# design.net
KiCad netlist of a schematic drawn in Altium Designer
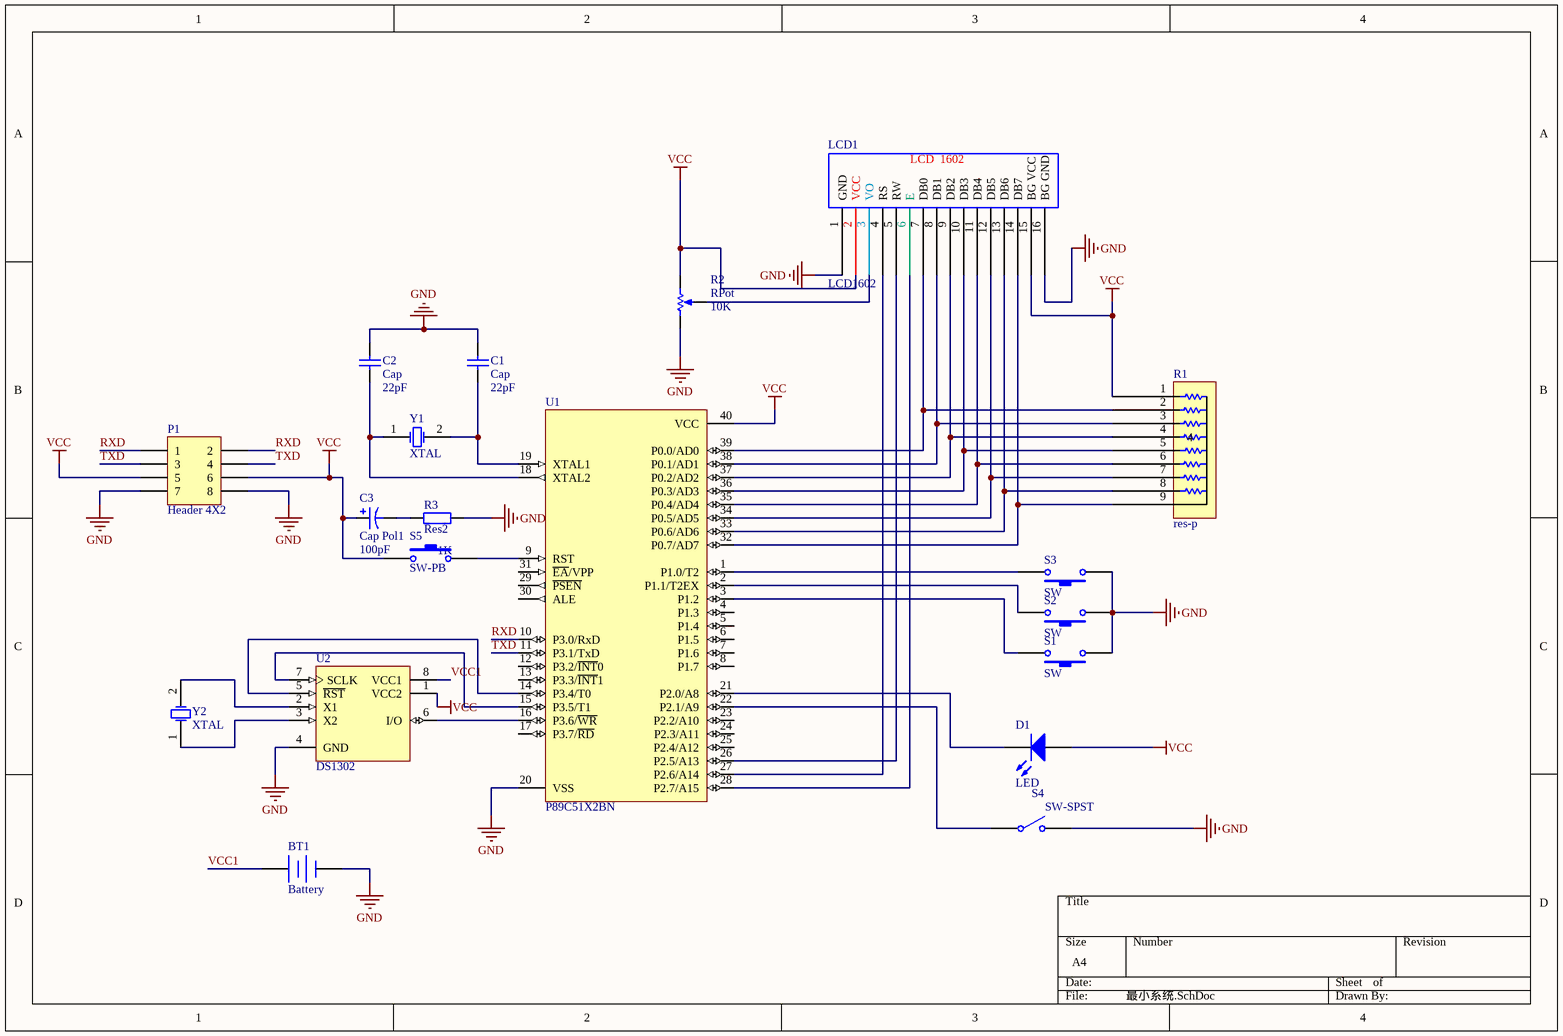
[diagram p0: 最小系统.SchDoc]

(export (version "E")
  (design (tool "Eeschema 10.0.6"))
  (components
    (comp (ref "BT1")
      (value "Battery")
      (footprint "BAT-2")
      (description "Multicell Battery")
      (fields (field (name "PUBLISHER") "Altium Limited"))
      (libsource (lib "Miscellaneous Devices") (part "Battery"))
    )
    (comp (ref "C1")
      (value "Cap")
      (footprint "CAPR2.54-5.1x3.2")
      (description "Capacitor")
      (fields (field (name "ALTIUM_VALUE") "22pF") (field (name "PUBLISHER") "Altium Limited"))
      (libsource (lib "Miscellaneous Devices") (part "Cap"))
    )
    (comp (ref "C2")
      (value "Cap")
      (footprint "CAPR2.54-5.1x3.2")
      (description "Capacitor")
      (fields (field (name "ALTIUM_VALUE") "22pF") (field (name "PUBLISHER") "Altium Limited"))
      (libsource (lib "Miscellaneous Devices") (part "Cap"))
    )
    (comp (ref "C3")
      (value "Cap Pol1")
      (footprint "RB7.6-15")
      (description "Polarized Capacitor (Radial)")
      (fields (field (name "ALTIUM_VALUE") "100pF") (field (name "PUBLISHER") "Altium Limited"))
      (libsource (lib "Miscellaneous Devices") (part "Cap Pol1"))
    )
    (comp (ref "D1") (value "LED") (footprint "LED-1") (libsource (lib "我的集成库库") (part "LED")))
    (comp (ref "LCD1") (value "LCD1602") (footprint "1602LCD") (libsource (lib "MyInt_Lib") (part "LCD1602")))
    (comp (ref "P1")
      (value "Header 4X2")
      (footprint "HDR2X4")
      (description "Header, 4-Pin, Dual row")
      (fields (field (name "PUBLISHER") "Altium Limited"))
      (libsource (lib "Miscellaneous Connectors") (part "Header 4X2"))
    )
    (comp (ref "R1") (value "res-p") (footprint "HDR1X9") (libsource (lib "我的集成库库") (part "res-p")))
    (comp (ref "R2")
      (value "RPot")
      (footprint "VR5")
      (description "Potentiometer")
      (fields (field (name "ALTIUM_VALUE") "10K") (field (name "PUBLISHER") "Altium Limited"))
      (libsource (lib "Miscellaneous Devices") (part "RPot"))
    )
    (comp (ref "R3")
      (value "Res2")
      (footprint "AXIAL-0.4")
      (description "Resistor")
      (fields (field (name "ALTIUM_VALUE") "1K") (field (name "PUBLISHER") "Altium Limited"))
      (libsource (lib "Miscellaneous Devices") (part "Res2"))
    )
    (comp (ref "S1") (value "SW") (footprint "SW/PB-V4/H7.1") (libsource (lib "我的集成库库") (part "SWITCH")))
    (comp (ref "S2") (value "SW") (footprint "SW/PB-V4/H7.1") (libsource (lib "我的集成库库") (part "SWITCH")))
    (comp (ref "S3") (value "SW") (footprint "SW/PB-V4/H7.1") (libsource (lib "我的集成库库") (part "SWITCH")))
    (comp (ref "S4")
      (value "SW-SPST")
      (footprint "SPST-2")
      (description "Single-Pole, Single-Throw Switch")
      (fields (field (name "PUBLISHER") "Altium Limited"))
      (libsource (lib "Miscellaneous Devices") (part "SW-SPST"))
    )
    (comp (ref "S5")
      (value "SW-PB")
      (footprint "SW/PB-V4/H7.1")
      (description "Switch")
      (fields (field (name "PUBLISHER") "Altium Limited"))
      (libsource (lib "Miscellaneous Devices") (part "SW-PB"))
    )
    (comp (ref "U1")
      (value "P89C51X2BN")
      (footprint "SOT129-1")
      (description "80C51 8-Bit Flash Microcontroller Family, 4 kB Flash")
      (fields (field (name "PUBLISHER") "Altium Limited"))
      (libsource (lib "Philips Microcontroller 8-Bit") (part "P89C51X2BN"))
    )
    (comp (ref "U2")
      (value "DS1302")
      (footprint "DIP8")
      (description "Trickle Charge Timekeeping Chip")
      (fields (field (name "PUBLISHER") "Altium Limited"))
      (libsource (lib "Dallas Peripheral Real Time Clock") (part "DS1302"))
    )
    (comp (ref "Y1")
      (value "XTAL")
      (footprint "BCY-W2/D3.1")
      (description "Crystal Oscillator")
      (fields (field (name "PUBLISHER") "Altium Limited"))
      (libsource (lib "Miscellaneous Devices") (part "XTAL"))
    )
    (comp (ref "Y2")
      (value "XTAL")
      (footprint "BCY-W2/D3.1")
      (description "Crystal Oscillator")
      (fields (field (name "PUBLISHER") "Altium Limited"))
      (libsource (lib "Miscellaneous Devices") (part "XTAL"))
    )
  )
  (nets
    (net (code "1") (name "/RXD") (class "Default")
      (node (ref "P1") (pin "1") (pinfunction "1_1") (pintype "passive"))
      (node (ref "P1") (pin "2") (pinfunction "2_2") (pintype "passive"))
      (node (ref "U1") (pin "10") (pinfunction "P3.0/RxD_10") (pintype "bidirectional"))
    )
    (net (code "2") (name "/TXD") (class "Default")
      (node (ref "P1") (pin "3") (pinfunction "3_3") (pintype "passive"))
      (node (ref "P1") (pin "4") (pinfunction "4_4") (pintype "passive"))
      (node (ref "U1") (pin "11") (pinfunction "P3.1/TxD_11") (pintype "bidirectional"))
    )
    (net (code "3") (name "/VCC1") (class "Default")
      (node (ref "BT1") (pin "1") (pinfunction "+_1") (pintype "passive"))
      (node (ref "U2") (pin "8") (pinfunction "VCC1_8") (pintype "power_in"))
    )
    (net (code "4") (name "GND") (class "Default")
      (node (ref "BT1") (pin "2") (pinfunction "-_2") (pintype "passive"))
      (node (ref "C1") (pin "2") (pinfunction "2_2") (pintype "passive"))
      (node (ref "C2") (pin "2") (pinfunction "2_2") (pintype "passive"))
      (node (ref "LCD1") (pin "1") (pinfunction "GND_1") (pintype "passive"))
      (node (ref "LCD1") (pin "16") (pinfunction "BG_GND_16") (pintype "passive"))
      (node (ref "P1") (pin "7") (pinfunction "7_7") (pintype "passive"))
      (node (ref "P1") (pin "8") (pinfunction "8_8") (pintype "passive"))
      (node (ref "R2") (pin "1") (pinfunction "TOP_1") (pintype "passive"))
      (node (ref "R3") (pin "2") (pinfunction "2_2") (pintype "passive"))
      (node (ref "S1") (pin "1") (pinfunction "1_1") (pintype "passive"))
      (node (ref "S2") (pin "1") (pinfunction "1_1") (pintype "passive"))
      (node (ref "S3") (pin "1") (pinfunction "1_1") (pintype "passive"))
      (node (ref "S4") (pin "2") (pinfunction "NO_2") (pintype "passive"))
      (node (ref "U1") (pin "20") (pinfunction "VSS_20") (pintype "power_in"))
      (node (ref "U2") (pin "4") (pinfunction "GND_4") (pintype "power_in"))
    )
    (net (code "5") (name "Net-(C3-Pad2)") (class "Default")
      (node (ref "C3") (pin "2") (pinfunction "2_2") (pintype "passive"))
      (node (ref "R3") (pin "1") (pinfunction "1_1") (pintype "passive"))
    )
    (net (code "6") (name "Net-(D1-K)") (class "Default")
      (node (ref "D1") (pin "2") (pinfunction "K_2") (pintype "passive"))
      (node (ref "U1") (pin "21") (pinfunction "P2.0/A8_21") (pintype "bidirectional"))
    )
    (net (code "7") (name "Net-(LCD1-DB0)") (class "Default")
      (node (ref "LCD1") (pin "7") (pinfunction "DB0_7") (pintype "passive"))
      (node (ref "R1") (pin "2") (pinfunction "2_2") (pintype "passive"))
      (node (ref "U1") (pin "39") (pinfunction "P0.0/AD0_39") (pintype "bidirectional"))
    )
    (net (code "8") (name "Net-(LCD1-DB1)") (class "Default")
      (node (ref "LCD1") (pin "8") (pinfunction "DB1_8") (pintype "passive"))
      (node (ref "R1") (pin "3") (pinfunction "3_3") (pintype "passive"))
      (node (ref "U1") (pin "38") (pinfunction "P0.1/AD1_38") (pintype "bidirectional"))
    )
    (net (code "9") (name "Net-(LCD1-DB2)") (class "Default")
      (node (ref "LCD1") (pin "9") (pinfunction "DB2_9") (pintype "passive"))
      (node (ref "R1") (pin "4") (pinfunction "4_4") (pintype "passive"))
      (node (ref "U1") (pin "37") (pinfunction "P0.2/AD2_37") (pintype "bidirectional"))
    )
    (net (code "10") (name "Net-(LCD1-DB3)") (class "Default")
      (node (ref "LCD1") (pin "10") (pinfunction "DB3_10") (pintype "passive"))
      (node (ref "R1") (pin "5") (pinfunction "5_5") (pintype "passive"))
      (node (ref "U1") (pin "36") (pinfunction "P0.3/AD3_36") (pintype "bidirectional"))
    )
    (net (code "11") (name "Net-(LCD1-DB4)") (class "Default")
      (node (ref "LCD1") (pin "11") (pinfunction "DB4_11") (pintype "passive"))
      (node (ref "R1") (pin "6") (pinfunction "6_6") (pintype "passive"))
      (node (ref "U1") (pin "35") (pinfunction "P0.4/AD4_35") (pintype "bidirectional"))
    )
    (net (code "12") (name "Net-(LCD1-DB5)") (class "Default")
      (node (ref "LCD1") (pin "12") (pinfunction "DB5_12") (pintype "passive"))
      (node (ref "R1") (pin "7") (pinfunction "7_7") (pintype "passive"))
      (node (ref "U1") (pin "34") (pinfunction "P0.5/AD5_34") (pintype "bidirectional"))
    )
    (net (code "13") (name "Net-(LCD1-DB6)") (class "Default")
      (node (ref "LCD1") (pin "13") (pinfunction "DB6_13") (pintype "passive"))
      (node (ref "R1") (pin "8") (pinfunction "8_8") (pintype "passive"))
      (node (ref "U1") (pin "33") (pinfunction "P0.6/AD6_33") (pintype "bidirectional"))
    )
    (net (code "14") (name "Net-(LCD1-DB7)") (class "Default")
      (node (ref "LCD1") (pin "14") (pinfunction "DB7_14") (pintype "passive"))
      (node (ref "R1") (pin "9") (pinfunction "9_9") (pintype "passive"))
      (node (ref "U1") (pin "32") (pinfunction "P0.7/AD7_32") (pintype "bidirectional"))
    )
    (net (code "15") (name "Net-(LCD1-E)") (class "Default")
      (node (ref "LCD1") (pin "6") (pinfunction "E_6") (pintype "passive"))
      (node (ref "U1") (pin "28") (pinfunction "P2.7/A15_28") (pintype "bidirectional"))
    )
    (net (code "16") (name "Net-(LCD1-RS)") (class "Default")
      (node (ref "LCD1") (pin "4") (pinfunction "RS_4") (pintype "passive"))
      (node (ref "U1") (pin "27") (pinfunction "P2.6/A14_27") (pintype "bidirectional"))
    )
    (net (code "17") (name "Net-(LCD1-RW)") (class "Default")
      (node (ref "LCD1") (pin "5") (pinfunction "RW_5") (pintype "passive"))
      (node (ref "U1") (pin "26") (pinfunction "P2.5/A13_26") (pintype "bidirectional"))
    )
    (net (code "18") (name "Net-(LCD1-VO)") (class "Default")
      (node (ref "LCD1") (pin "3") (pinfunction "VO_3") (pintype "passive"))
      (node (ref "R2") (pin "3") (pinfunction "TAP_3") (pintype "passive"))
    )
    (net (code "19") (name "Net-(S4-COMMON)") (class "Default")
      (node (ref "S4") (pin "1") (pinfunction "COMMON_1") (pintype "passive"))
      (node (ref "U1") (pin "22") (pinfunction "P2.1/A9_22") (pintype "bidirectional"))
    )
    (net (code "20") (name "Net-(U1-P1.0{slash}T2)") (class "Default")
      (node (ref "S3") (pin "2") (pinfunction "2_2") (pintype "passive"))
      (node (ref "U1") (pin "1") (pinfunction "P1.0/T2_1") (pintype "bidirectional"))
    )
    (net (code "21") (name "Net-(U1-P1.1{slash}T2EX)") (class "Default")
      (node (ref "S2") (pin "2") (pinfunction "2_2") (pintype "passive"))
      (node (ref "U1") (pin "2") (pinfunction "P1.1/T2EX_2") (pintype "bidirectional"))
    )
    (net (code "22") (name "Net-(U1-P1.2)") (class "Default")
      (node (ref "S1") (pin "2") (pinfunction "2_2") (pintype "passive"))
      (node (ref "U1") (pin "3") (pinfunction "P1.2_3") (pintype "bidirectional"))
    )
    (net (code "23") (name "Net-(U1-P3.4{slash}T0)") (class "Default")
      (node (ref "U1") (pin "14") (pinfunction "P3.4/T0_14") (pintype "bidirectional"))
      (node (ref "U2") (pin "5") (pinfunction "~{RST}_5") (pintype "input"))
    )
    (net (code "24") (name "Net-(U1-P3.5{slash}T1)") (class "Default")
      (node (ref "U1") (pin "15") (pinfunction "P3.5/T1_15") (pintype "bidirectional"))
      (node (ref "U2") (pin "7") (pinfunction "SCLK_7") (pintype "input"))
    )
    (net (code "25") (name "Net-(U1-P3.6{slash}~{WR})") (class "Default")
      (node (ref "U1") (pin "16") (pinfunction "P3.6/~{WR}_16") (pintype "bidirectional"))
      (node (ref "U2") (pin "6") (pinfunction "I/O_6") (pintype "bidirectional"))
    )
    (net (code "26") (name "Net-(U1-RST)") (class "Default")
      (node (ref "S5") (pin "2") (pinfunction "2_2") (pintype "passive"))
      (node (ref "U1") (pin "9") (pinfunction "RST_9") (pintype "input"))
    )
    (net (code "27") (name "Net-(U1-XTAL1)") (class "Default")
      (node (ref "C1") (pin "1") (pinfunction "1_1") (pintype "passive"))
      (node (ref "U1") (pin "19") (pinfunction "XTAL1_19") (pintype "input"))
      (node (ref "Y1") (pin "2") (pinfunction "OSC2_2") (pintype "passive"))
    )
    (net (code "28") (name "Net-(U1-XTAL2)") (class "Default")
      (node (ref "C2") (pin "1") (pinfunction "1_1") (pintype "passive"))
      (node (ref "U1") (pin "18") (pinfunction "XTAL2_18") (pintype "output"))
      (node (ref "Y1") (pin "1") (pinfunction "OSC1_1") (pintype "passive"))
    )
    (net (code "29") (name "Net-(U2-X1)") (class "Default")
      (node (ref "U2") (pin "2") (pinfunction "X1_2") (pintype "input"))
      (node (ref "Y2") (pin "2") (pinfunction "OSC2_2") (pintype "passive"))
    )
    (net (code "30") (name "Net-(U2-X2)") (class "Default")
      (node (ref "U2") (pin "3") (pinfunction "X2_3") (pintype "input"))
      (node (ref "Y2") (pin "1") (pinfunction "OSC1_1") (pintype "passive"))
    )
    (net (code "31") (name "VCC") (class "Default")
      (node (ref "C3") (pin "1") (pinfunction "1_1") (pintype "passive"))
      (node (ref "D1") (pin "1") (pinfunction "A_1") (pintype "passive"))
      (node (ref "LCD1") (pin "15") (pinfunction "BG_VCC_15") (pintype "passive"))
      (node (ref "LCD1") (pin "2") (pinfunction "VCC_2") (pintype "passive"))
      (node (ref "P1") (pin "5") (pinfunction "5_5") (pintype "passive"))
      (node (ref "P1") (pin "6") (pinfunction "6_6") (pintype "passive"))
      (node (ref "R1") (pin "1") (pinfunction "1_1") (pintype "passive"))
      (node (ref "R2") (pin "2") (pinfunction "BOT_2") (pintype "passive"))
      (node (ref "S5") (pin "1") (pinfunction "1_1") (pintype "passive"))
      (node (ref "U1") (pin "40") (pinfunction "VCC_40") (pintype "power_in"))
      (node (ref "U2") (pin "1") (pinfunction "VCC2_1") (pintype "power_in"))
    )
    (net (code "32") (name "unconnected-(U1-ALE-Pad30)") (class "Default")
      (node (ref "U1") (pin "30") (pinfunction "ALE_30") (pintype "output"))
    )
    (net (code "33") (name "unconnected-(U1-P1.3-Pad4)") (class "Default")
      (node (ref "U1") (pin "4") (pinfunction "P1.3_4") (pintype "bidirectional"))
    )
    (net (code "34") (name "unconnected-(U1-P1.4-Pad5)") (class "Default")
      (node (ref "U1") (pin "5") (pinfunction "P1.4_5") (pintype "bidirectional"))
    )
    (net (code "35") (name "unconnected-(U1-P1.5-Pad6)") (class "Default")
      (node (ref "U1") (pin "6") (pinfunction "P1.5_6") (pintype "bidirectional"))
    )
    (net (code "36") (name "unconnected-(U1-P1.6-Pad7)") (class "Default")
      (node (ref "U1") (pin "7") (pinfunction "P1.6_7") (pintype "bidirectional"))
    )
    (net (code "37") (name "unconnected-(U1-P1.7-Pad8)") (class "Default")
      (node (ref "U1") (pin "8") (pinfunction "P1.7_8") (pintype "bidirectional"))
    )
    (net (code "38") (name "unconnected-(U1-P2.2{slash}A10-Pad23)") (class "Default")
      (node (ref "U1") (pin "23") (pinfunction "P2.2/A10_23") (pintype "bidirectional"))
    )
    (net (code "39") (name "unconnected-(U1-P2.3{slash}A11-Pad24)") (class "Default")
      (node (ref "U1") (pin "24") (pinfunction "P2.3/A11_24") (pintype "bidirectional"))
    )
    (net (code "40") (name "unconnected-(U1-P2.4{slash}A12-Pad25)") (class "Default")
      (node (ref "U1") (pin "25") (pinfunction "P2.4/A12_25") (pintype "bidirectional"))
    )
    (net (code "41") (name "unconnected-(U1-P3.2{slash}~{INT}0-Pad12)") (class "Default")
      (node (ref "U1") (pin "12") (pinfunction "P3.2/~{INT}0_12") (pintype "bidirectional"))
    )
    (net (code "42") (name "unconnected-(U1-P3.3{slash}~{INT}1-Pad13)") (class "Default")
      (node (ref "U1") (pin "13") (pinfunction "P3.3/~{INT}1_13") (pintype "bidirectional"))
    )
    (net (code "43") (name "unconnected-(U1-P3.7{slash}~{RD}-Pad17)") (class "Default")
      (node (ref "U1") (pin "17") (pinfunction "P3.7/~{RD}_17") (pintype "bidirectional"))
    )
    (net (code "44") (name "unconnected-(U1-~{EA}{slash}VPP-Pad31)") (class "Default")
      (node (ref "U1") (pin "31") (pinfunction "~{EA}/VPP_31") (pintype "input"))
    )
    (net (code "45") (name "unconnected-(U1-~{PSEN}-Pad29)") (class "Default")
      (node (ref "U1") (pin "29") (pinfunction "~{PSEN}_29") (pintype "output"))
    )
  )
)
